# 1_ESP8266_Hot_Plate.net
KiCad netlist of a schematic drawn in Altium Designer
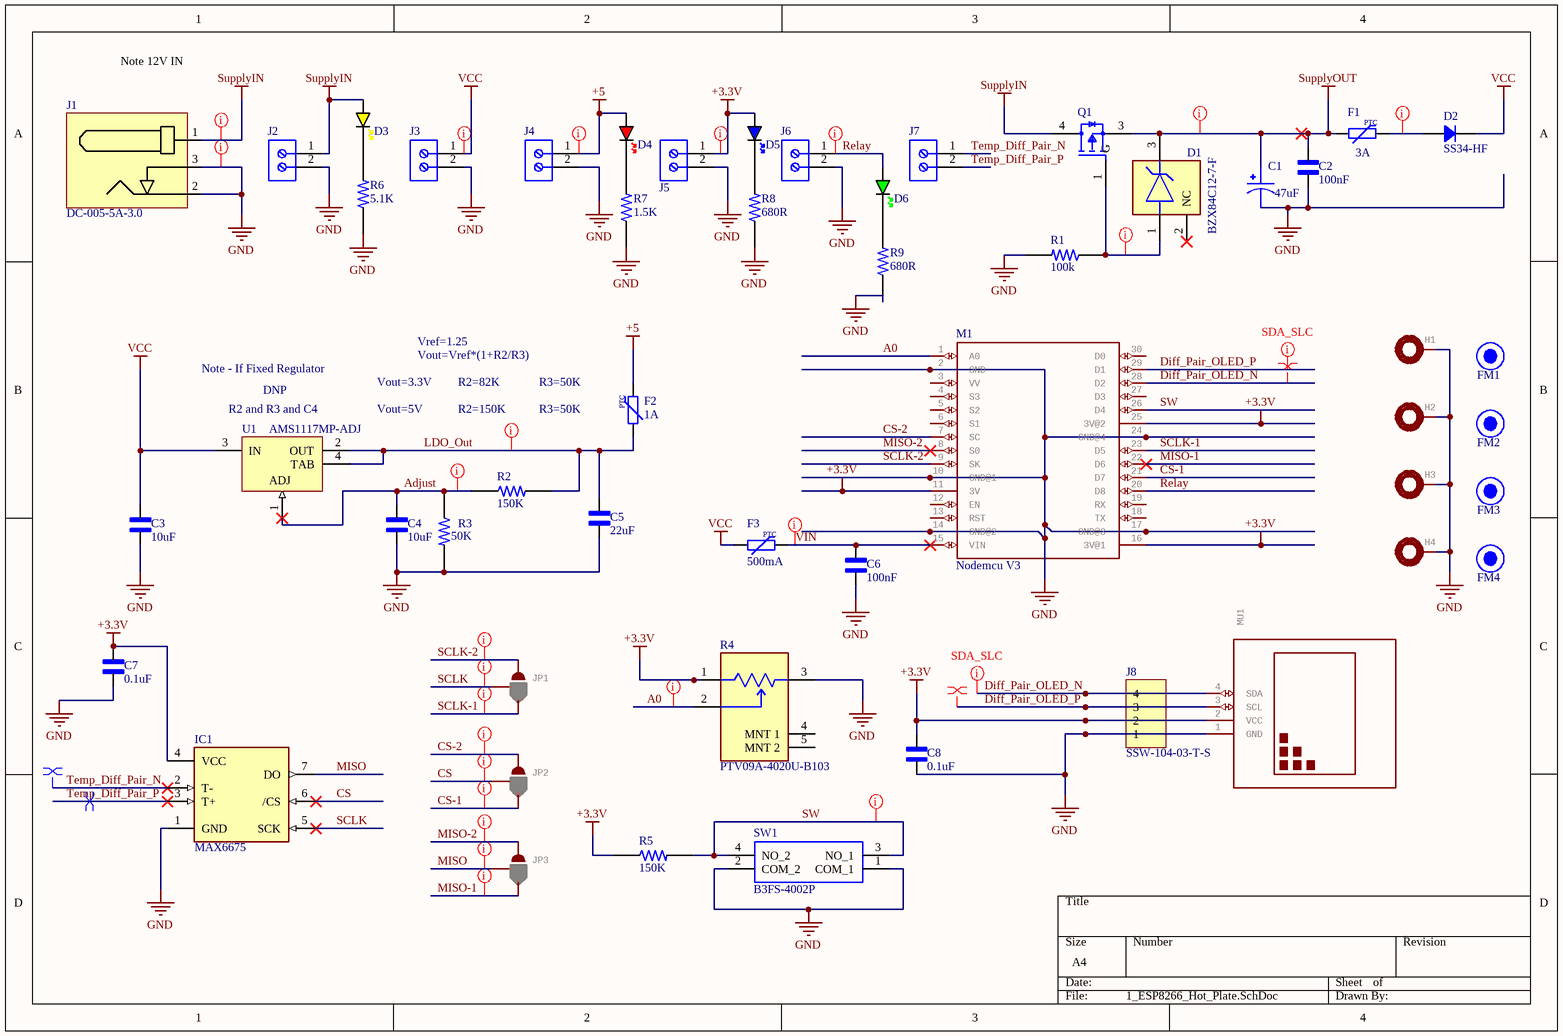
[diagram p0: 1_ESP8266_Hot_Plate.SchDoc]

(export (version "E")
  (design (tool "Eeschema 10.0.6"))
  (components
    (comp (ref "C1")
      (value "47uF")
      (footprint "1411-3528")
      (description "Molded Tantalum Capacitors 16V 1411 (3528 Metric)")
      (fields (field (name "MF") "KEMET") (field (name "MP") "T495B106K025ATE750"))
      (libsource (lib "ESP8266_Hot_Plate") (part "C-1411 (3528 Metric)"))
    )
    (comp (ref "C2")
      (value "100nF")
      (footprint "C-0603")
      (description "Ceramic Capacitor 16V 0603 (1608 Metric)")
      (fields (field (name "MP") "C0603C104J4RAC") (field (name "MF") "KEMET"))
      (libsource (lib "ESP8266_Hot_Plate") (part "C-0603"))
    )
    (comp (ref "C3")
      (value "10uF")
      (footprint "C-0603")
      (description "Ceramic Capacitor 16V 0603 (1608 Metric)")
      (fields (field (name "MP") "C0603C104J4RAC") (field (name "MF") "KEMET"))
      (libsource (lib "ESP8266_Hot_Plate") (part "C-0603"))
    )
    (comp (ref "C4")
      (value "10uF")
      (footprint "C-0603")
      (description "Ceramic Capacitor 16V 0603 (1608 Metric)")
      (fields (field (name "MP") "C0603C104J4RAC") (field (name "MF") "KEMET"))
      (libsource (lib "ESP8266_Hot_Plate") (part "C-0603"))
    )
    (comp (ref "C5")
      (value "22uF")
      (footprint "C-0603")
      (description "Ceramic Capacitor 16V 0603 (1608 Metric)")
      (fields (field (name "MP") "C0603C104J4RAC") (field (name "MF") "KEMET"))
      (libsource (lib "ESP8266_Hot_Plate") (part "C-0603"))
    )
    (comp (ref "C6")
      (value "100nF")
      (footprint "C-0603")
      (description "Ceramic Capacitor 16V 0603 (1608 Metric)")
      (fields (field (name "MP") "C0603C104J4RAC") (field (name "MF") "KEMET"))
      (libsource (lib "ESP8266_Hot_Plate") (part "C-0603"))
    )
    (comp (ref "C7")
      (value "0.1uF")
      (footprint "C-0603")
      (description "Ceramic Capacitor 16V 0603 (1608 Metric)")
      (fields (field (name "MP") "C0603C104J4RAC") (field (name "MF") "KEMET"))
      (libsource (lib "ESP8266_Hot_Plate") (part "C-0603"))
    )
    (comp (ref "C8")
      (value "0.1uF")
      (footprint "C-0603")
      (description "Ceramic Capacitor 16V 0603 (1608 Metric)")
      (fields (field (name "MP") "C0603C104J4RAC") (field (name "MF") "KEMET"))
      (libsource (lib "ESP8266_Hot_Plate") (part "C-0603"))
    )
    (comp (ref "D1")
      (value "BZX84C12-7-F")
      (footprint "FP-SOT23-MFG")
      (description "DIODE ZENER 12V 300MW SOT23-3")
      (fields
        (field (name "OCTOPART") "https://octopart.com/bzx84c12-7-f-diodes+inc.-327696")
        (field (name "MANUFACTURER") "Diodes Inc.")
      )
      (libsource (lib "ESP8266_Hot_Plate") (part "4a6bcd6c75a58f30e1c7f5dd6419ea8"))
    )
    (comp (ref "D2")
      (value "SS34-HF")
      (footprint "DO214AC SMA")
      (description "DIODE SCHOTTKY 40V 3A DO214AC")
      (fields (field (name "MANUFACTURER") "Comchip Technology"))
      (libsource (lib "ESP8266_Hot_Plate") (part "Diode"))
    )
    (comp (ref "D3")
      (value "YELLOW")
      (footprint "LED_0603_YELLOW")
      (description "LED 0603 YELLOW SMD")
      (libsource (lib "ESP8266_Hot_Plate") (part "LED_0603_YELLOW"))
    )
    (comp (ref "D4")
      (value "RED")
      (footprint "LED_0603_RED")
      (description "LED 0603 RED SMD")
      (libsource (lib "ESP8266_Hot_Plate") (part "LED_0603_RED"))
    )
    (comp (ref "D5")
      (value "BLUE")
      (footprint "LED_0603_BLUE")
      (description "LED 0603 BLUE SMD")
      (libsource (lib "ESP8266_Hot_Plate") (part "LED_0603_BLUE"))
    )
    (comp (ref "D6")
      (value "GREEN")
      (footprint "LED_0603_GREEN")
      (description "LED 0603 GREEN SMD")
      (libsource (lib "ESP8266_Hot_Plate") (part "LED_0603_GREEN"))
    )
    (comp (ref "F1")
      (value "3A")
      (footprint "FUSE_1206")
      (description "Fuse PPTC SMD 1206")
      (libsource (lib "ESP8266_Hot_Plate") (part "FUSE_PPTC_1206"))
    )
    (comp (ref "F2")
      (value "1A")
      (footprint "FUSE_1206")
      (description "Fuse PPTC SMD 1206")
      (libsource (lib "ESP8266_Hot_Plate") (part "FUSE_PPTC_1206"))
    )
    (comp (ref "F3")
      (value "500mA")
      (footprint "FUSE_1206")
      (description "Fuse PPTC SMD 1206")
      (libsource (lib "ESP8266_Hot_Plate") (part "FUSE_PPTC_1206"))
    )
    (comp (ref "FM1")
      (value "FIDUCIAL")
      (footprint "FIDUCIAL-1MM")
      (libsource (lib "ESP8266_Hot_Plate") (part "FIDUCIAL"))
    )
    (comp (ref "FM2")
      (value "FIDUCIAL")
      (footprint "FIDUCIAL-1MM")
      (libsource (lib "ESP8266_Hot_Plate") (part "FIDUCIAL"))
    )
    (comp (ref "FM3")
      (value "FIDUCIAL")
      (footprint "FIDUCIAL-1MM")
      (libsource (lib "ESP8266_Hot_Plate") (part "FIDUCIAL"))
    )
    (comp (ref "FM4")
      (value "FIDUCIAL")
      (footprint "FIDUCIAL-1MM")
      (libsource (lib "ESP8266_Hot_Plate") (part "FIDUCIAL"))
    )
    (comp (ref "H1")
      (value "MOUNTING PAD, round")
      (footprint "2,4-PAD")
      (libsource (lib "ESP8266_Hot_Plate") (part "MOUNT-PAD-ROUND2.4"))
    )
    (comp (ref "H2")
      (value "MOUNTING PAD, round")
      (footprint "2,4-PAD")
      (libsource (lib "ESP8266_Hot_Plate") (part "MOUNT-PAD-ROUND2.4"))
    )
    (comp (ref "H3")
      (value "MOUNTING PAD, round")
      (footprint "2,4-PAD")
      (libsource (lib "ESP8266_Hot_Plate") (part "MOUNT-PAD-ROUND2.4"))
    )
    (comp (ref "H4")
      (value "MOUNTING PAD, round")
      (footprint "2,4-PAD")
      (libsource (lib "ESP8266_Hot_Plate") (part "MOUNT-PAD-ROUND2.4"))
    )
    (comp (ref "IC1")
      (value "MAX6675")
      (footprint "SO08")
      (description "IC THERMOCOUP TO DGTL 8-SOIC")
      (fields (field (name "MF") "Maxim Integrated"))
      (libsource (lib "ESP8266_Hot_Plate") (part "MAX6675"))
    )
    (comp (ref "J1")
      (value "DC-005-5A-3.0")
      (footprint "DC-005-5A-3.0")
      (description "DC Barrell Jack 6.2mm 5 A3.0mm Through Hole")
      (libsource (lib "ESP8266_Hot_Plate") (part "DC-005-5A-3.0"))
    )
    (comp (ref "J2")
      (value "691214110002")
      (footprint "691214110002")
      (description "Serie 2141 - 3.50 mm Horizontal Entry Modular with Rising Cage Clamp WR-TBL, 2 pin")
      (fields (field (name "MANUFACTURER") "Wurth Elektronik") (field (name "PUBLISHER") "WurthElektronik"))
      (libsource (lib "ESP8266_Hot_Plate") (part "WE-CN-1P-F-TB2"))
    )
    (comp (ref "J3")
      (value "691214110002")
      (footprint "691214110002")
      (description "Serie 2141 - 3.50 mm Horizontal Entry Modular with Rising Cage Clamp WR-TBL, 2 pin")
      (fields (field (name "MANUFACTURER") "Wurth Elektronik") (field (name "PUBLISHER") "WurthElektronik"))
      (libsource (lib "ESP8266_Hot_Plate") (part "WE-CN-1P-F-TB2"))
    )
    (comp (ref "J4")
      (value "691214110002")
      (footprint "691214110002")
      (description "Serie 2141 - 3.50 mm Horizontal Entry Modular with Rising Cage Clamp WR-TBL, 2 pin")
      (fields (field (name "MANUFACTURER") "Wurth Elektronik") (field (name "PUBLISHER") "WurthElektronik"))
      (libsource (lib "ESP8266_Hot_Plate") (part "WE-CN-1P-F-TB2"))
    )
    (comp (ref "J5")
      (value "691214110002")
      (footprint "691214110002")
      (description "Serie 2141 - 3.50 mm Horizontal Entry Modular with Rising Cage Clamp WR-TBL, 2 pin")
      (fields (field (name "MANUFACTURER") "Wurth Elektronik") (field (name "PUBLISHER") "WurthElektronik"))
      (libsource (lib "ESP8266_Hot_Plate") (part "WE-CN-1P-F-TB2"))
    )
    (comp (ref "J6")
      (value "691214110002")
      (footprint "691214110002")
      (description "Serie 2141 - 3.50 mm Horizontal Entry Modular with Rising Cage Clamp WR-TBL, 2 pin")
      (fields (field (name "MANUFACTURER") "Wurth Elektronik") (field (name "PUBLISHER") "WurthElektronik"))
      (libsource (lib "ESP8266_Hot_Plate") (part "WE-CN-1P-F-TB2"))
    )
    (comp (ref "J7")
      (value "691214110002")
      (footprint "691214110002")
      (description "Serie 2141 - 3.50 mm Horizontal Entry Modular with Rising Cage Clamp WR-TBL, 2 pin")
      (fields (field (name "MANUFACTURER") "Wurth Elektronik") (field (name "PUBLISHER") "WurthElektronik"))
      (libsource (lib "ESP8266_Hot_Plate") (part "WE-CN-1P-F-TB2"))
    )
    (comp (ref "J8")
      (value "SSW-104-03-T-S")
      (footprint "SAMTEC SSW-104-03-T-S")
      (description "CONN RCPT 4POS 0.1 TIN PCB")
      (fields (field (name "MANUFACTURER") "Samtec Inc."))
      (libsource (lib "ESP8266_Hot_Plate") (part "4 Pin"))
    )
    (comp (ref "JP1")
      (value "JUMPER-SMT_3_1-NC_PASTE_SILK")
      (footprint "SMT-JUMPER_3_1-NC_PASTE_SILK")
      (libsource (lib "ESP8266_Hot_Plate") (part "JUMPER-SMT_3_1-NC_PASTE_SILK"))
    )
    (comp (ref "JP2")
      (value "JUMPER-SMT_3_1-NC_PASTE_SILK")
      (footprint "SMT-JUMPER_3_1-NC_PASTE_SILK")
      (libsource (lib "ESP8266_Hot_Plate") (part "JUMPER-SMT_3_1-NC_PASTE_SILK"))
    )
    (comp (ref "JP3")
      (value "JUMPER-SMT_3_1-NC_PASTE_SILK")
      (footprint "SMT-JUMPER_3_1-NC_PASTE_SILK")
      (libsource (lib "ESP8266_Hot_Plate") (part "JUMPER-SMT_3_1-NC_PASTE_SILK"))
    )
    (comp (ref "M1")
      (value "Nodemcu V3")
      (footprint "NODEMCU")
      (description "Node MCU V3 Module")
      (libsource (lib "ESP8266_Hot_Plate") (part "NODEMCU"))
    )
    (comp (ref "MU1")
      (value "128x64 Dot Matrix OLED Module based on SSD1306")
      (footprint "DISPLAY-OLED-128X64-I2C")
      (libsource (lib "ESP8266_Hot_Plate") (part "DISPLAY-OLED-128X64-I2C"))
    )
    (comp (ref "Q1")
      (value "FDD6637")
      (footprint "FP-369AS-MFG")
      (description "MOSFET P-CH 35V 13A DPAK")
      (fields
        (field (name "OCTOPART") "https://octopart.com/fdd6637-on+semiconductor-84325825")
        (field (name "MANUFACTURER") "ON Semiconductor")
      )
      (libsource (lib "ESP8266_Hot_Plate") (part "cee2e0b37b8b7601ebfb19aba2d2b4e"))
    )
    (comp (ref "R1")
      (value "100k")
      (footprint "R-0603")
      (description "0603")
      (fields (field (name "MP") "2-1623703-0") (field (name "TOLERANCE") "1%"))
      (libsource (lib "ESP8266_Hot_Plate") (part "R-0603"))
    )
    (comp (ref "R2")
      (value "150K")
      (footprint "R-0603")
      (description "0603")
      (fields (field (name "MP") "2-1623703-0") (field (name "TOLERANCE") "1%"))
      (libsource (lib "ESP8266_Hot_Plate") (part "R-0603"))
    )
    (comp (ref "R3")
      (value "50K")
      (footprint "R-0603")
      (description "0603")
      (fields (field (name "MP") "2-1623703-0") (field (name "TOLERANCE") "1%"))
      (libsource (lib "ESP8266_Hot_Plate") (part "R-0603"))
    )
    (comp (ref "R4")
      (value "PTV09A-4020U-B103")
      (footprint "FP-PTV09A-4-MFG")
      (description "POT 10K OHM 1/20W CARBON LINEAR")
      (fields (field (name "TOLERANCE") "20%") (field (name "MANUFACTURER") "Bourns Inc."))
      (libsource (lib "ESP8266_Hot_Plate") (part "3454c451b146ec4d4239c7813666f62"))
    )
    (comp (ref "R5")
      (value "150K")
      (footprint "R-0603")
      (description "0603")
      (fields (field (name "MP") "2-1623703-0") (field (name "TOLERANCE") "1%"))
      (libsource (lib "ESP8266_Hot_Plate") (part "R-0603"))
    )
    (comp (ref "R6")
      (value "5.1K")
      (footprint "R-0603")
      (description "0603")
      (fields (field (name "MP") "2-1623703-0") (field (name "TOLERANCE") "1%"))
      (libsource (lib "ESP8266_Hot_Plate") (part "R-0603"))
    )
    (comp (ref "R7")
      (value "1.5K")
      (footprint "R-0603")
      (description "0603")
      (fields (field (name "MP") "2-1623703-0") (field (name "TOLERANCE") "1%"))
      (libsource (lib "ESP8266_Hot_Plate") (part "R-0603"))
    )
    (comp (ref "R8")
      (value "680R")
      (footprint "R-0603")
      (description "0603")
      (fields (field (name "MP") "2-1623703-0") (field (name "TOLERANCE") "1%"))
      (libsource (lib "ESP8266_Hot_Plate") (part "R-0603"))
    )
    (comp (ref "R9")
      (value "680R")
      (footprint "R-0603")
      (description "0603")
      (fields (field (name "MP") "2-1623703-0") (field (name "TOLERANCE") "1%"))
      (libsource (lib "ESP8266_Hot_Plate") (part "R-0603"))
    )
    (comp (ref "SW1")
      (value "B3FS-4002P")
      (footprint "B3FS4002P")
      (description "Black Cap Tactile Switch, SPST-NO 50 mA @ 24 V dc 0.4mm")
      (fields (field (name "MOUSER PART NUMBER") "653-B3FS-4002P"))
      (libsource (lib "ESP8266_Hot_Plate") (part "Tactile Switch 12x12mm"))
    )
    (comp (ref "U1")
      (value "AMS1117MP-ADJ")
      (footprint "MP04A_N")
      (description "800mA Low-Dropout Linear Regulator, 4-pin SOT-223")
      (fields
        (field (name "PARTNUMBER") "LM1117MP-ADJ")
        (field (name "MANUFACTURER") "National Semiconductor")
      )
      (libsource (lib "ESP8266_Hot_Plate") (part "PM-REG-LM1086ADJ-SOT4"))
    )
  )
  (nets
    (net (code "1") (name "+3.3V") (class "Default")
      (node (ref "C7") (pin "2") (pinfunction "2_2") (pintype "passive"))
      (node (ref "C8") (pin "2") (pinfunction "2_2") (pintype "passive"))
      (node (ref "D5") (pin "A") (pinfunction "A_A") (pintype "passive"))
      (node (ref "IC1") (pin "4") (pinfunction "VCC_4") (pintype "power_in"))
      (node (ref "J5") (pin "1") (pinfunction "1_1") (pintype "passive"))
      (node (ref "J8") (pin "2") (pinfunction "2_2") (pintype "passive"))
      (node (ref "M1") (pin "11") (pinfunction "3V_11") (pintype "power_in"))
      (node (ref "M1") (pin "16") (pinfunction "3V@1_16") (pintype "power_in"))
      (node (ref "M1") (pin "25") (pinfunction "3V@2_25") (pintype "power_in"))
      (node (ref "MU1") (pin "2") (pinfunction "VCC_2") (pintype "power_in"))
      (node (ref "R4") (pin "1") (pinfunction "1_1") (pintype "passive"))
      (node (ref "R5") (pin "1") (pinfunction "1_1") (pintype "passive"))
    )
    (net (code "2") (name "+5") (class "Default")
      (node (ref "D4") (pin "A") (pinfunction "A_A") (pintype "passive"))
      (node (ref "F2") (pin "2") (pinfunction "2_2") (pintype "passive"))
      (node (ref "J4") (pin "1") (pinfunction "1_1") (pintype "passive"))
    )
    (net (code "3") (name "/A0") (class "Default")
      (node (ref "M1") (pin "1") (pinfunction "A0_1") (pintype "bidirectional"))
      (node (ref "R4") (pin "2") (pinfunction "2_2") (pintype "passive"))
    )
    (net (code "4") (name "/Adjust") (class "Default")
      (node (ref "C4") (pin "2") (pinfunction "2_2") (pintype "passive"))
      (node (ref "R2") (pin "1") (pinfunction "1_1") (pintype "passive"))
      (node (ref "R3") (pin "1") (pinfunction "1_1") (pintype "passive"))
      (node (ref "U1") (pin "1") (pinfunction "ADJ_1") (pintype "input"))
    )
    (net (code "5") (name "/CS") (class "Default")
      (node (ref "IC1") (pin "6") (pinfunction "/CS_6") (pintype "input"))
      (node (ref "JP2") (pin "2") (pinfunction "2_2") (pintype "passive"))
    )
    (net (code "6") (name "/CS-1") (class "Default")
      (node (ref "JP2") (pin "3") (pinfunction "3_3") (pintype "passive"))
      (node (ref "M1") (pin "21") (pinfunction "D7_21") (pintype "bidirectional"))
    )
    (net (code "7") (name "/CS-2") (class "Default")
      (node (ref "JP2") (pin "1") (pinfunction "1_1") (pintype "passive"))
      (node (ref "M1") (pin "7") (pinfunction "SC_7") (pintype "bidirectional"))
    )
    (net (code "8") (name "/Diff_Pair_OLED_N") (class "Default")
      (node (ref "J8") (pin "4") (pinfunction "4_4") (pintype "passive"))
      (node (ref "M1") (pin "28") (pinfunction "D2_28") (pintype "bidirectional"))
      (node (ref "MU1") (pin "4") (pinfunction "SDA_4") (pintype "bidirectional"))
    )
    (net (code "9") (name "/Diff_Pair_OLED_P") (class "Default")
      (node (ref "J8") (pin "3") (pinfunction "3_3") (pintype "passive"))
      (node (ref "M1") (pin "29") (pinfunction "D1_29") (pintype "bidirectional"))
      (node (ref "MU1") (pin "3") (pinfunction "SCL_3") (pintype "bidirectional"))
    )
    (net (code "10") (name "/LDO_Out") (class "Default")
      (node (ref "C5") (pin "2") (pinfunction "2_2") (pintype "passive"))
      (node (ref "F2") (pin "1") (pinfunction "1_1") (pintype "passive"))
      (node (ref "R2") (pin "2") (pinfunction "2_2") (pintype "passive"))
      (node (ref "U1") (pin "2") (pinfunction "OUT_2") (pintype "power_in"))
      (node (ref "U1") (pin "4") (pinfunction "TAB_4") (pintype "power_in"))
    )
    (net (code "11") (name "/MISO") (class "Default")
      (node (ref "IC1") (pin "7") (pinfunction "DO_7") (pintype "output"))
      (node (ref "JP3") (pin "2") (pinfunction "2_2") (pintype "passive"))
    )
    (net (code "12") (name "/MISO-1") (class "Default")
      (node (ref "JP3") (pin "3") (pinfunction "3_3") (pintype "passive"))
      (node (ref "M1") (pin "22") (pinfunction "D6_22") (pintype "bidirectional"))
    )
    (net (code "13") (name "/MISO-2") (class "Default")
      (node (ref "JP3") (pin "1") (pinfunction "1_1") (pintype "passive"))
      (node (ref "M1") (pin "8") (pinfunction "S0_8") (pintype "bidirectional"))
    )
    (net (code "14") (name "/Relay") (class "Default")
      (node (ref "D6") (pin "A") (pinfunction "A_A") (pintype "passive"))
      (node (ref "J6") (pin "1") (pinfunction "1_1") (pintype "passive"))
      (node (ref "M1") (pin "20") (pinfunction "D8_20") (pintype "bidirectional"))
    )
    (net (code "15") (name "/SCLK") (class "Default")
      (node (ref "IC1") (pin "5") (pinfunction "SCK_5") (pintype "input"))
      (node (ref "JP1") (pin "2") (pinfunction "2_2") (pintype "passive"))
    )
    (net (code "16") (name "/SCLK-1") (class "Default")
      (node (ref "JP1") (pin "3") (pinfunction "3_3") (pintype "passive"))
      (node (ref "M1") (pin "23") (pinfunction "D5_23") (pintype "bidirectional"))
    )
    (net (code "17") (name "/SCLK-2") (class "Default")
      (node (ref "JP1") (pin "1") (pinfunction "1_1") (pintype "passive"))
      (node (ref "M1") (pin "9") (pinfunction "SK_9") (pintype "bidirectional"))
    )
    (net (code "18") (name "/SW") (class "Default")
      (node (ref "M1") (pin "26") (pinfunction "D4_26") (pintype "bidirectional"))
      (node (ref "R5") (pin "2") (pinfunction "2_2") (pintype "passive"))
      (node (ref "SW1") (pin "3") (pinfunction "NO_1_3") (pintype "passive"))
      (node (ref "SW1") (pin "4") (pinfunction "NO_2_4") (pintype "passive"))
    )
    (net (code "19") (name "/Temp_Diff_Pair_N") (class "Default")
      (node (ref "IC1") (pin "2") (pinfunction "T-_2") (pintype "input"))
      (node (ref "J7") (pin "1") (pinfunction "1_1") (pintype "passive"))
    )
    (net (code "20") (name "/Temp_Diff_Pair_P") (class "Default")
      (node (ref "IC1") (pin "3") (pinfunction "T+_3") (pintype "input"))
      (node (ref "J7") (pin "2") (pinfunction "2_2") (pintype "passive"))
    )
    (net (code "21") (name "/VIN") (class "Default")
      (node (ref "C6") (pin "2") (pinfunction "2_2") (pintype "passive"))
      (node (ref "F3") (pin "2") (pinfunction "2_2") (pintype "passive"))
      (node (ref "M1") (pin "15") (pinfunction "VIN_15") (pintype "bidirectional"))
    )
    (net (code "22") (name "GND") (class "Default")
      (node (ref "C1") (pin "2") (pinfunction "2_2") (pintype "passive"))
      (node (ref "C2") (pin "1") (pinfunction "1_1") (pintype "passive"))
      (node (ref "C3") (pin "1") (pinfunction "1_1") (pintype "passive"))
      (node (ref "C4") (pin "1") (pinfunction "1_1") (pintype "passive"))
      (node (ref "C5") (pin "1") (pinfunction "1_1") (pintype "passive"))
      (node (ref "C6") (pin "1") (pinfunction "1_1") (pintype "passive"))
      (node (ref "C7") (pin "1") (pinfunction "1_1") (pintype "passive"))
      (node (ref "C8") (pin "1") (pinfunction "1_1") (pintype "passive"))
      (node (ref "H1") (pin "1") (pinfunction "MOUNT_1") (pintype "passive"))
      (node (ref "H2") (pin "1") (pinfunction "MOUNT_1") (pintype "passive"))
      (node (ref "H3") (pin "1") (pinfunction "MOUNT_1") (pintype "passive"))
      (node (ref "H4") (pin "1") (pinfunction "MOUNT_1") (pintype "passive"))
      (node (ref "IC1") (pin "1") (pinfunction "GND_1") (pintype "power_in"))
      (node (ref "J1") (pin "2") (pinfunction "2_2") (pintype "passive"))
      (node (ref "J1") (pin "3") (pinfunction "3_3") (pintype "passive"))
      (node (ref "J2") (pin "2") (pinfunction "2_2") (pintype "passive"))
      (node (ref "J3") (pin "2") (pinfunction "2_2") (pintype "passive"))
      (node (ref "J4") (pin "2") (pinfunction "2_2") (pintype "passive"))
      (node (ref "J5") (pin "2") (pinfunction "2_2") (pintype "passive"))
      (node (ref "J6") (pin "2") (pinfunction "2_2") (pintype "passive"))
      (node (ref "J8") (pin "1") (pinfunction "1_1") (pintype "passive"))
      (node (ref "M1") (pin "10") (pinfunction "GND@1_10") (pintype "power_in"))
      (node (ref "M1") (pin "14") (pinfunction "GND@2_14") (pintype "power_in"))
      (node (ref "M1") (pin "17") (pinfunction "GND@3_17") (pintype "power_in"))
      (node (ref "M1") (pin "2") (pinfunction "GND_2") (pintype "power_in"))
      (node (ref "M1") (pin "24") (pinfunction "GND@4_24") (pintype "power_in"))
      (node (ref "MU1") (pin "1") (pinfunction "GND_1") (pintype "power_in"))
      (node (ref "R1") (pin "2") (pinfunction "2_2") (pintype "passive"))
      (node (ref "R3") (pin "2") (pinfunction "2_2") (pintype "passive"))
      (node (ref "R4") (pin "3") (pinfunction "3_3") (pintype "passive"))
      (node (ref "R6") (pin "1") (pinfunction "1_1") (pintype "passive"))
      (node (ref "R7") (pin "1") (pinfunction "1_1") (pintype "passive"))
      (node (ref "R8") (pin "1") (pinfunction "1_1") (pintype "passive"))
      (node (ref "R9") (pin "1") (pinfunction "1_1") (pintype "passive"))
      (node (ref "SW1") (pin "1") (pinfunction "COM_1_1") (pintype "passive"))
      (node (ref "SW1") (pin "2") (pinfunction "COM_2_2") (pintype "passive"))
    )
    (net (code "23") (name "Net-(D1-A)") (class "Default")
      (node (ref "D1") (pin "1") (pinfunction "A_1") (pintype "passive"))
      (node (ref "Q1") (pin "1") (pinfunction "G_1") (pintype "passive"))
      (node (ref "R1") (pin "1") (pinfunction "1_1") (pintype "passive"))
    )
    (net (code "24") (name "Net-(D2-Pad1)") (class "Default")
      (node (ref "D2") (pin "1") (pinfunction "1_1") (pintype "passive"))
      (node (ref "F1") (pin "2") (pinfunction "2_2") (pintype "passive"))
    )
    (net (code "25") (name "Net-(D3-PadK)") (class "Default")
      (node (ref "D3") (pin "K") (pinfunction "K_K") (pintype "passive"))
      (node (ref "R6") (pin "2") (pinfunction "2_2") (pintype "passive"))
    )
    (net (code "26") (name "Net-(D4-PadK)") (class "Default")
      (node (ref "D4") (pin "K") (pinfunction "K_K") (pintype "passive"))
      (node (ref "R7") (pin "2") (pinfunction "2_2") (pintype "passive"))
    )
    (net (code "27") (name "Net-(D5-PadK)") (class "Default")
      (node (ref "D5") (pin "K") (pinfunction "K_K") (pintype "passive"))
      (node (ref "R8") (pin "2") (pinfunction "2_2") (pintype "passive"))
    )
    (net (code "28") (name "Net-(D6-PadK)") (class "Default")
      (node (ref "D6") (pin "K") (pinfunction "K_K") (pintype "passive"))
      (node (ref "R9") (pin "2") (pinfunction "2_2") (pintype "passive"))
    )
    (net (code "29") (name "SupplyIN") (class "Default")
      (node (ref "D3") (pin "A") (pinfunction "A_A") (pintype "passive"))
      (node (ref "J1") (pin "1") (pinfunction "1_1") (pintype "passive"))
      (node (ref "J2") (pin "1") (pinfunction "1_1") (pintype "passive"))
      (node (ref "Q1") (pin "4") (pinfunction "D_4") (pintype "passive"))
    )
    (net (code "30") (name "SupplyOUT") (class "Default")
      (node (ref "C1") (pin "1") (pinfunction "1_1") (pintype "passive"))
      (node (ref "C2") (pin "2") (pinfunction "2_2") (pintype "passive"))
      (node (ref "D1") (pin "3") (pinfunction "C_3") (pintype "passive"))
      (node (ref "F1") (pin "1") (pinfunction "1_1") (pintype "passive"))
      (node (ref "Q1") (pin "3") (pinfunction "S_3") (pintype "passive"))
    )
    (net (code "31") (name "VCC") (class "Default")
      (node (ref "C3") (pin "2") (pinfunction "2_2") (pintype "passive"))
      (node (ref "D2") (pin "2") (pinfunction "2_2") (pintype "passive"))
      (node (ref "F3") (pin "1") (pinfunction "1_1") (pintype "passive"))
      (node (ref "J3") (pin "1") (pinfunction "1_1") (pintype "passive"))
      (node (ref "U1") (pin "3") (pinfunction "IN_3") (pintype "power_in"))
    )
    (net (code "32") (name "unconnected-(D1-NC-Pad2)") (class "Default")
      (node (ref "D1") (pin "2") (pinfunction "NC_2") (pintype "passive+no_connect"))
    )
    (net (code "33") (name "unconnected-(M1-D0-Pad30)") (class "Default")
      (node (ref "M1") (pin "30") (pinfunction "D0_30") (pintype "bidirectional"))
    )
    (net (code "34") (name "unconnected-(M1-D3-Pad27)") (class "Default")
      (node (ref "M1") (pin "27") (pinfunction "D3_27") (pintype "bidirectional"))
    )
    (net (code "35") (name "unconnected-(M1-EN-Pad12)") (class "Default")
      (node (ref "M1") (pin "12") (pinfunction "EN_12") (pintype "bidirectional"))
    )
    (net (code "36") (name "unconnected-(M1-RST-Pad13)") (class "Default")
      (node (ref "M1") (pin "13") (pinfunction "RST_13") (pintype "bidirectional"))
    )
    (net (code "37") (name "unconnected-(M1-RX-Pad19)") (class "Default")
      (node (ref "M1") (pin "19") (pinfunction "RX_19") (pintype "bidirectional"))
    )
    (net (code "38") (name "unconnected-(M1-S1-Pad6)") (class "Default")
      (node (ref "M1") (pin "6") (pinfunction "S1_6") (pintype "bidirectional"))
    )
    (net (code "39") (name "unconnected-(M1-S2-Pad5)") (class "Default")
      (node (ref "M1") (pin "5") (pinfunction "S2_5") (pintype "bidirectional"))
    )
    (net (code "40") (name "unconnected-(M1-S3-Pad4)") (class "Default")
      (node (ref "M1") (pin "4") (pinfunction "S3_4") (pintype "bidirectional"))
    )
    (net (code "41") (name "unconnected-(M1-TX-Pad18)") (class "Default")
      (node (ref "M1") (pin "18") (pinfunction "TX_18") (pintype "bidirectional"))
    )
    (net (code "42") (name "unconnected-(M1-VV-Pad3)") (class "Default")
      (node (ref "M1") (pin "3") (pinfunction "VV_3") (pintype "bidirectional"))
    )
    (net (code "43") (name "unconnected-(R4-MNT_1-Pad4)") (class "Default")
      (node (ref "R4") (pin "4") (pinfunction "MNT_1_4") (pintype "passive"))
    )
    (net (code "44") (name "unconnected-(R4-MNT_2-Pad5)") (class "Default")
      (node (ref "R4") (pin "5") (pinfunction "MNT_2_5") (pintype "passive"))
    )
  )
)
